# ECG.net
KiCad netlist of a schematic drawn in Altium Designer
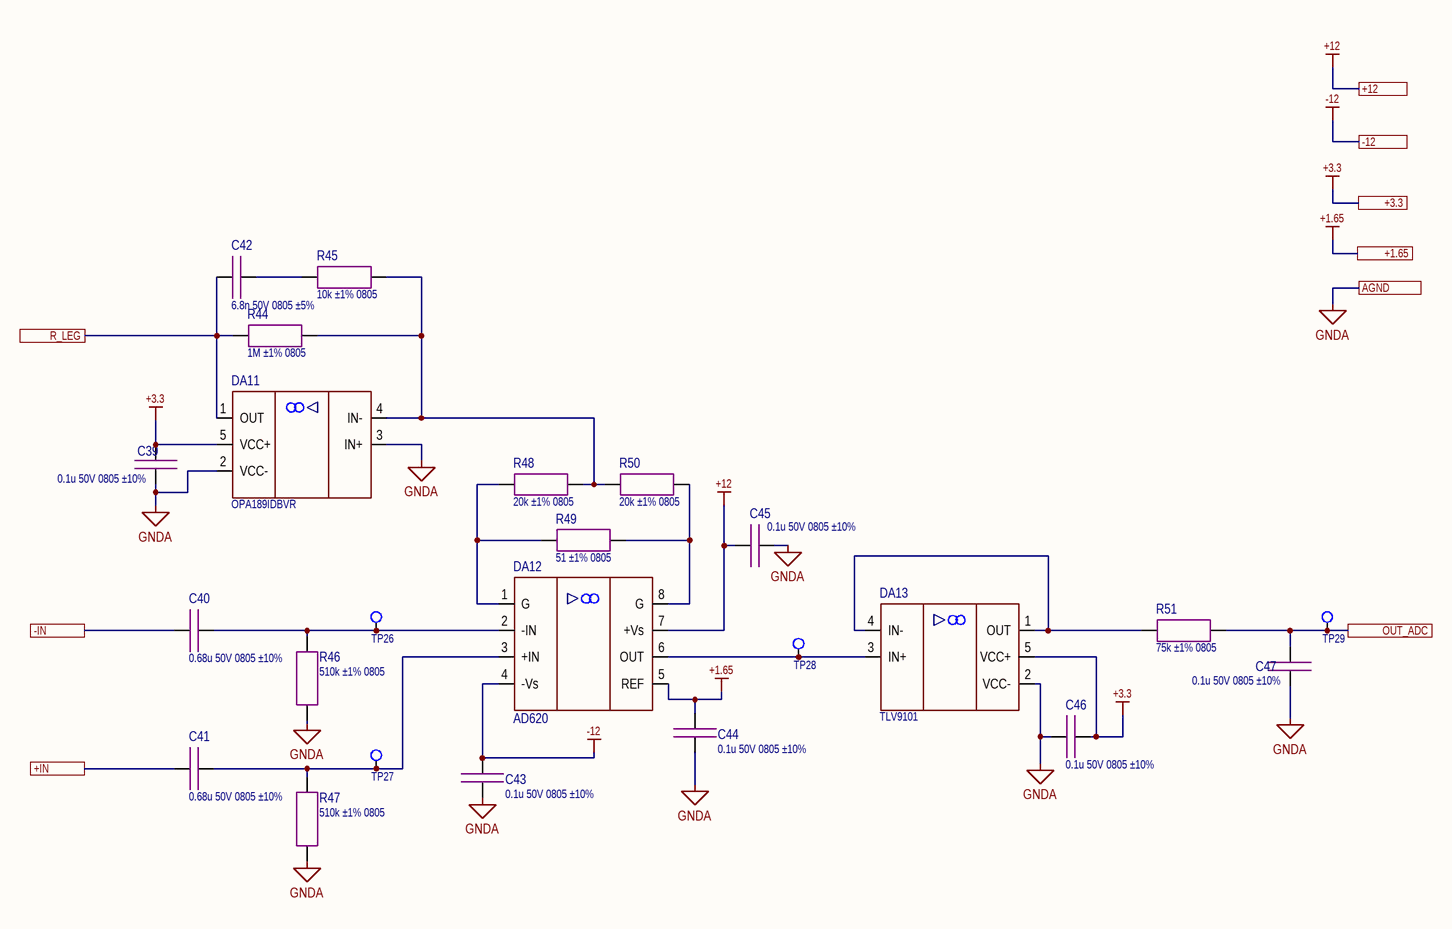
[diagram p0: ECG.SchDoc]

(export (version "E")
  (design (tool "Eeschema 10.0.6"))
  (components
    (comp (ref "C39")
      (value "0.1u 50V 0805 ±10%")
      (footprint "CAP: SMD 0805 MD IPC 782")
      (libsource (lib "UOMP capacitors") (part "0.1u 50V 0805 ±10%"))
    )
    (comp (ref "C40")
      (value "0.68u 50V 0805 ±10%")
      (footprint "CAP: SMD 0805 MD IPC 782")
      (libsource (lib "UOMP capacitors") (part "0.68u 50V 0805 ±10%"))
    )
    (comp (ref "C41")
      (value "0.68u 50V 0805 ±10%")
      (footprint "CAP: SMD 0805 MD IPC 782")
      (libsource (lib "UOMP capacitors") (part "0.68u 50V 0805 ±10%"))
    )
    (comp (ref "C42")
      (value "6.8n 50V 0805 ±5%")
      (footprint "CAP: SMD 0805 MD IPC 782")
      (libsource (lib "UOMP capacitors") (part "6.8n 50V 0805 ±5%"))
    )
    (comp (ref "C43")
      (value "0.1u 50V 0805 ±10%")
      (footprint "CAP: SMD 0805 MD IPC 782")
      (libsource (lib "UOMP capacitors") (part "0.1u 50V 0805 ±10%"))
    )
    (comp (ref "C44")
      (value "0.1u 50V 0805 ±10%")
      (footprint "CAP: SMD 0805 MD IPC 782")
      (libsource (lib "UOMP capacitors") (part "0.1u 50V 0805 ±10%"))
    )
    (comp (ref "C45")
      (value "0.1u 50V 0805 ±10%")
      (footprint "CAP: SMD 0805 MD IPC 782")
      (libsource (lib "UOMP capacitors") (part "0.1u 50V 0805 ±10%"))
    )
    (comp (ref "C46")
      (value "0.1u 50V 0805 ±10%")
      (footprint "CAP: SMD 0805 MD IPC 782")
      (libsource (lib "UOMP capacitors") (part "0.1u 50V 0805 ±10%"))
    )
    (comp (ref "C47")
      (value "0.1u 50V 0805 ±10%")
      (footprint "CAP: SMD 0805 MD IPC 782")
      (libsource (lib "UOMP capacitors") (part "0.1u 50V 0805 ±10%"))
    )
    (comp (ref "DA11")
      (value "OPA189IDBVR")
      (footprint "IC: SOT 23 5pin")
      (libsource (lib "UOMP operational amplifier") (part "OPA189IDBVR"))
    )
    (comp (ref "DA12")
      (value "AD620")
      (footprint "IC: SOIC 8")
      (libsource (lib "UOMP operational amplifier") (part "AD620"))
    )
    (comp (ref "DA13")
      (value "TLV9101")
      (footprint "IC: SOT 23 5pin")
      (libsource (lib "UOMP operational amplifier") (part "TLV9101"))
    )
    (comp (ref "R44")
      (value "1M ±1% 0805")
      (footprint "RES: SMD 0805 MD IPC 782")
      (libsource (lib "UOMP resistors") (part "1M ±1% 0805"))
    )
    (comp (ref "R45")
      (value "10k ±1% 0805")
      (footprint "RES: SMD 0805 MD IPC 782")
      (libsource (lib "UOMP resistors") (part "10k ±1% 0805"))
    )
    (comp (ref "R46")
      (value "510k ±1% 0805")
      (footprint "RES: SMD 0805 MD IPC 782")
      (libsource (lib "UOMP resistors") (part "510k ±1% 0805"))
    )
    (comp (ref "R47")
      (value "510k ±1% 0805")
      (footprint "RES: SMD 0805 MD IPC 782")
      (libsource (lib "UOMP resistors") (part "510k ±1% 0805"))
    )
    (comp (ref "R48")
      (value "20k ±1% 0805")
      (footprint "RES: SMD 0805 MD IPC 782")
      (libsource (lib "UOMP resistors") (part "20k ±1% 0805"))
    )
    (comp (ref "R49")
      (value "51 ±1% 0805")
      (footprint "RES: SMD 0805 MD IPC 782")
      (libsource (lib "UOMP resistors") (part "51 ±1% 0805"))
    )
    (comp (ref "R50")
      (value "20k ±1% 0805")
      (footprint "RES: SMD 0805 MD IPC 782")
      (libsource (lib "UOMP resistors") (part "20k ±1% 0805"))
    )
    (comp (ref "R51")
      (value "75k ±1% 0805")
      (footprint "RES: SMD 0805 MD IPC 782")
      (libsource (lib "UOMP resistors") (part "75k ±1% 0805"))
    )
    (comp (ref "TP26")
      (value "Test point")
      (footprint "Test Point")
      (libsource (lib "UOMP_primitives") (part "Test point"))
    )
    (comp (ref "TP27")
      (value "Test point")
      (footprint "Test Point")
      (libsource (lib "UOMP_primitives") (part "Test point"))
    )
    (comp (ref "TP28")
      (value "Test point")
      (footprint "Test Point")
      (libsource (lib "UOMP_primitives") (part "Test point"))
    )
    (comp (ref "TP29")
      (value "Test point")
      (footprint "Test Point")
      (libsource (lib "UOMP_primitives") (part "Test point"))
    )
  )
  (nets
    (net (code "1") (name "+1.65") (class "Default")
      (node (ref "C44") (pin "2") (pinfunction "2_2") (pintype "passive"))
      (node (ref "DA12") (pin "5") (pinfunction "REF_5") (pintype "passive"))
    )
    (net (code "2") (name "+3.3") (class "Default")
      (node (ref "C39") (pin "1") (pinfunction "1_1") (pintype "passive"))
      (node (ref "C46") (pin "1") (pinfunction "1_1") (pintype "passive"))
      (node (ref "DA11") (pin "5") (pinfunction "VCC+_5") (pintype "passive"))
      (node (ref "DA13") (pin "5") (pinfunction "VCC+_5") (pintype "passive"))
    )
    (net (code "3") (name "+12") (class "Default")
      (node (ref "C45") (pin "1") (pinfunction "1_1") (pintype "passive"))
      (node (ref "DA12") (pin "7") (pinfunction "+Vs_7") (pintype "passive"))
    )
    (net (code "4") (name "-12") (class "Default")
      (node (ref "C43") (pin "1") (pinfunction "1_1") (pintype "passive"))
      (node (ref "DA12") (pin "4") (pinfunction "-Vs_4") (pintype "passive"))
    )
    (net (code "5") (name "/+IN") (class "Default")
      (node (ref "C41") (pin "2") (pinfunction "2_2") (pintype "passive"))
    )
    (net (code "6") (name "/-IN") (class "Default")
      (node (ref "C40") (pin "2") (pinfunction "2_2") (pintype "passive"))
    )
    (net (code "7") (name "/OUT_ADC") (class "Default")
      (node (ref "C47") (pin "1") (pinfunction "1_1") (pintype "passive"))
      (node (ref "R51") (pin "2") (pinfunction "2_2") (pintype "passive"))
      (node (ref "TP29") (pin "1") (pinfunction "1_1") (pintype "passive"))
    )
    (net (code "8") (name "/R_LEG") (class "Default")
      (node (ref "C42") (pin "2") (pinfunction "2_2") (pintype "passive"))
      (node (ref "DA11") (pin "1") (pinfunction "OUT_1") (pintype "passive"))
      (node (ref "R44") (pin "1") (pinfunction "1_1") (pintype "passive"))
    )
    (net (code "9") (name "GNDA") (class "Default")
      (node (ref "C39") (pin "2") (pinfunction "2_2") (pintype "passive"))
      (node (ref "C43") (pin "2") (pinfunction "2_2") (pintype "passive"))
      (node (ref "C44") (pin "1") (pinfunction "1_1") (pintype "passive"))
      (node (ref "C45") (pin "2") (pinfunction "2_2") (pintype "passive"))
      (node (ref "C46") (pin "2") (pinfunction "2_2") (pintype "passive"))
      (node (ref "C47") (pin "2") (pinfunction "2_2") (pintype "passive"))
      (node (ref "DA11") (pin "2") (pinfunction "VCC-_2") (pintype "passive"))
      (node (ref "DA11") (pin "3") (pinfunction "IN+_3") (pintype "passive"))
      (node (ref "DA13") (pin "2") (pinfunction "VCC-_2") (pintype "passive"))
      (node (ref "R46") (pin "1") (pinfunction "1_1") (pintype "passive"))
      (node (ref "R47") (pin "1") (pinfunction "1_1") (pintype "passive"))
    )
    (net (code "10") (name "Net-(C42-Pad1)") (class "Default")
      (node (ref "C42") (pin "1") (pinfunction "1_1") (pintype "passive"))
      (node (ref "R45") (pin "1") (pinfunction "1_1") (pintype "passive"))
    )
    (net (code "11") (name "Net-(DA11-IN-)") (class "Default")
      (node (ref "DA11") (pin "4") (pinfunction "IN-_4") (pintype "passive"))
      (node (ref "R44") (pin "2") (pinfunction "2_2") (pintype "passive"))
      (node (ref "R45") (pin "2") (pinfunction "2_2") (pintype "passive"))
      (node (ref "R48") (pin "2") (pinfunction "2_2") (pintype "passive"))
      (node (ref "R50") (pin "1") (pinfunction "1_1") (pintype "passive"))
    )
    (net (code "12") (name "Net-(DA12-+IN)") (class "Default")
      (node (ref "C41") (pin "1") (pinfunction "1_1") (pintype "passive"))
      (node (ref "DA12") (pin "3") (pinfunction "+IN_3") (pintype "passive"))
      (node (ref "R47") (pin "2") (pinfunction "2_2") (pintype "passive"))
      (node (ref "TP27") (pin "1") (pinfunction "1_1") (pintype "passive"))
    )
    (net (code "13") (name "Net-(DA12--IN)") (class "Default")
      (node (ref "C40") (pin "1") (pinfunction "1_1") (pintype "passive"))
      (node (ref "DA12") (pin "2") (pinfunction "-IN_2") (pintype "passive"))
      (node (ref "R46") (pin "2") (pinfunction "2_2") (pintype "passive"))
      (node (ref "TP26") (pin "1") (pinfunction "1_1") (pintype "passive"))
    )
    (net (code "14") (name "Net-(DA12-G-Pad1)") (class "Default")
      (node (ref "DA12") (pin "1") (pinfunction "G_1") (pintype "passive"))
      (node (ref "R48") (pin "1") (pinfunction "1_1") (pintype "passive"))
      (node (ref "R49") (pin "1") (pinfunction "1_1") (pintype "passive"))
    )
    (net (code "15") (name "Net-(DA12-G-Pad8)") (class "Default")
      (node (ref "DA12") (pin "8") (pinfunction "G_8") (pintype "passive"))
      (node (ref "R49") (pin "2") (pinfunction "2_2") (pintype "passive"))
      (node (ref "R50") (pin "2") (pinfunction "2_2") (pintype "passive"))
    )
    (net (code "16") (name "Net-(DA12-OUT)") (class "Default")
      (node (ref "DA12") (pin "6") (pinfunction "OUT_6") (pintype "passive"))
      (node (ref "DA13") (pin "3") (pinfunction "IN+_3") (pintype "passive"))
      (node (ref "TP28") (pin "1") (pinfunction "1_1") (pintype "passive"))
    )
    (net (code "17") (name "Net-(DA13-IN-)") (class "Default")
      (node (ref "DA13") (pin "1") (pinfunction "OUT_1") (pintype "passive"))
      (node (ref "DA13") (pin "4") (pinfunction "IN-_4") (pintype "passive"))
      (node (ref "R51") (pin "1") (pinfunction "1_1") (pintype "passive"))
    )
  )
)
